# FPGA_Configuration.net
KiCad netlist of a schematic drawn in Altium Designer
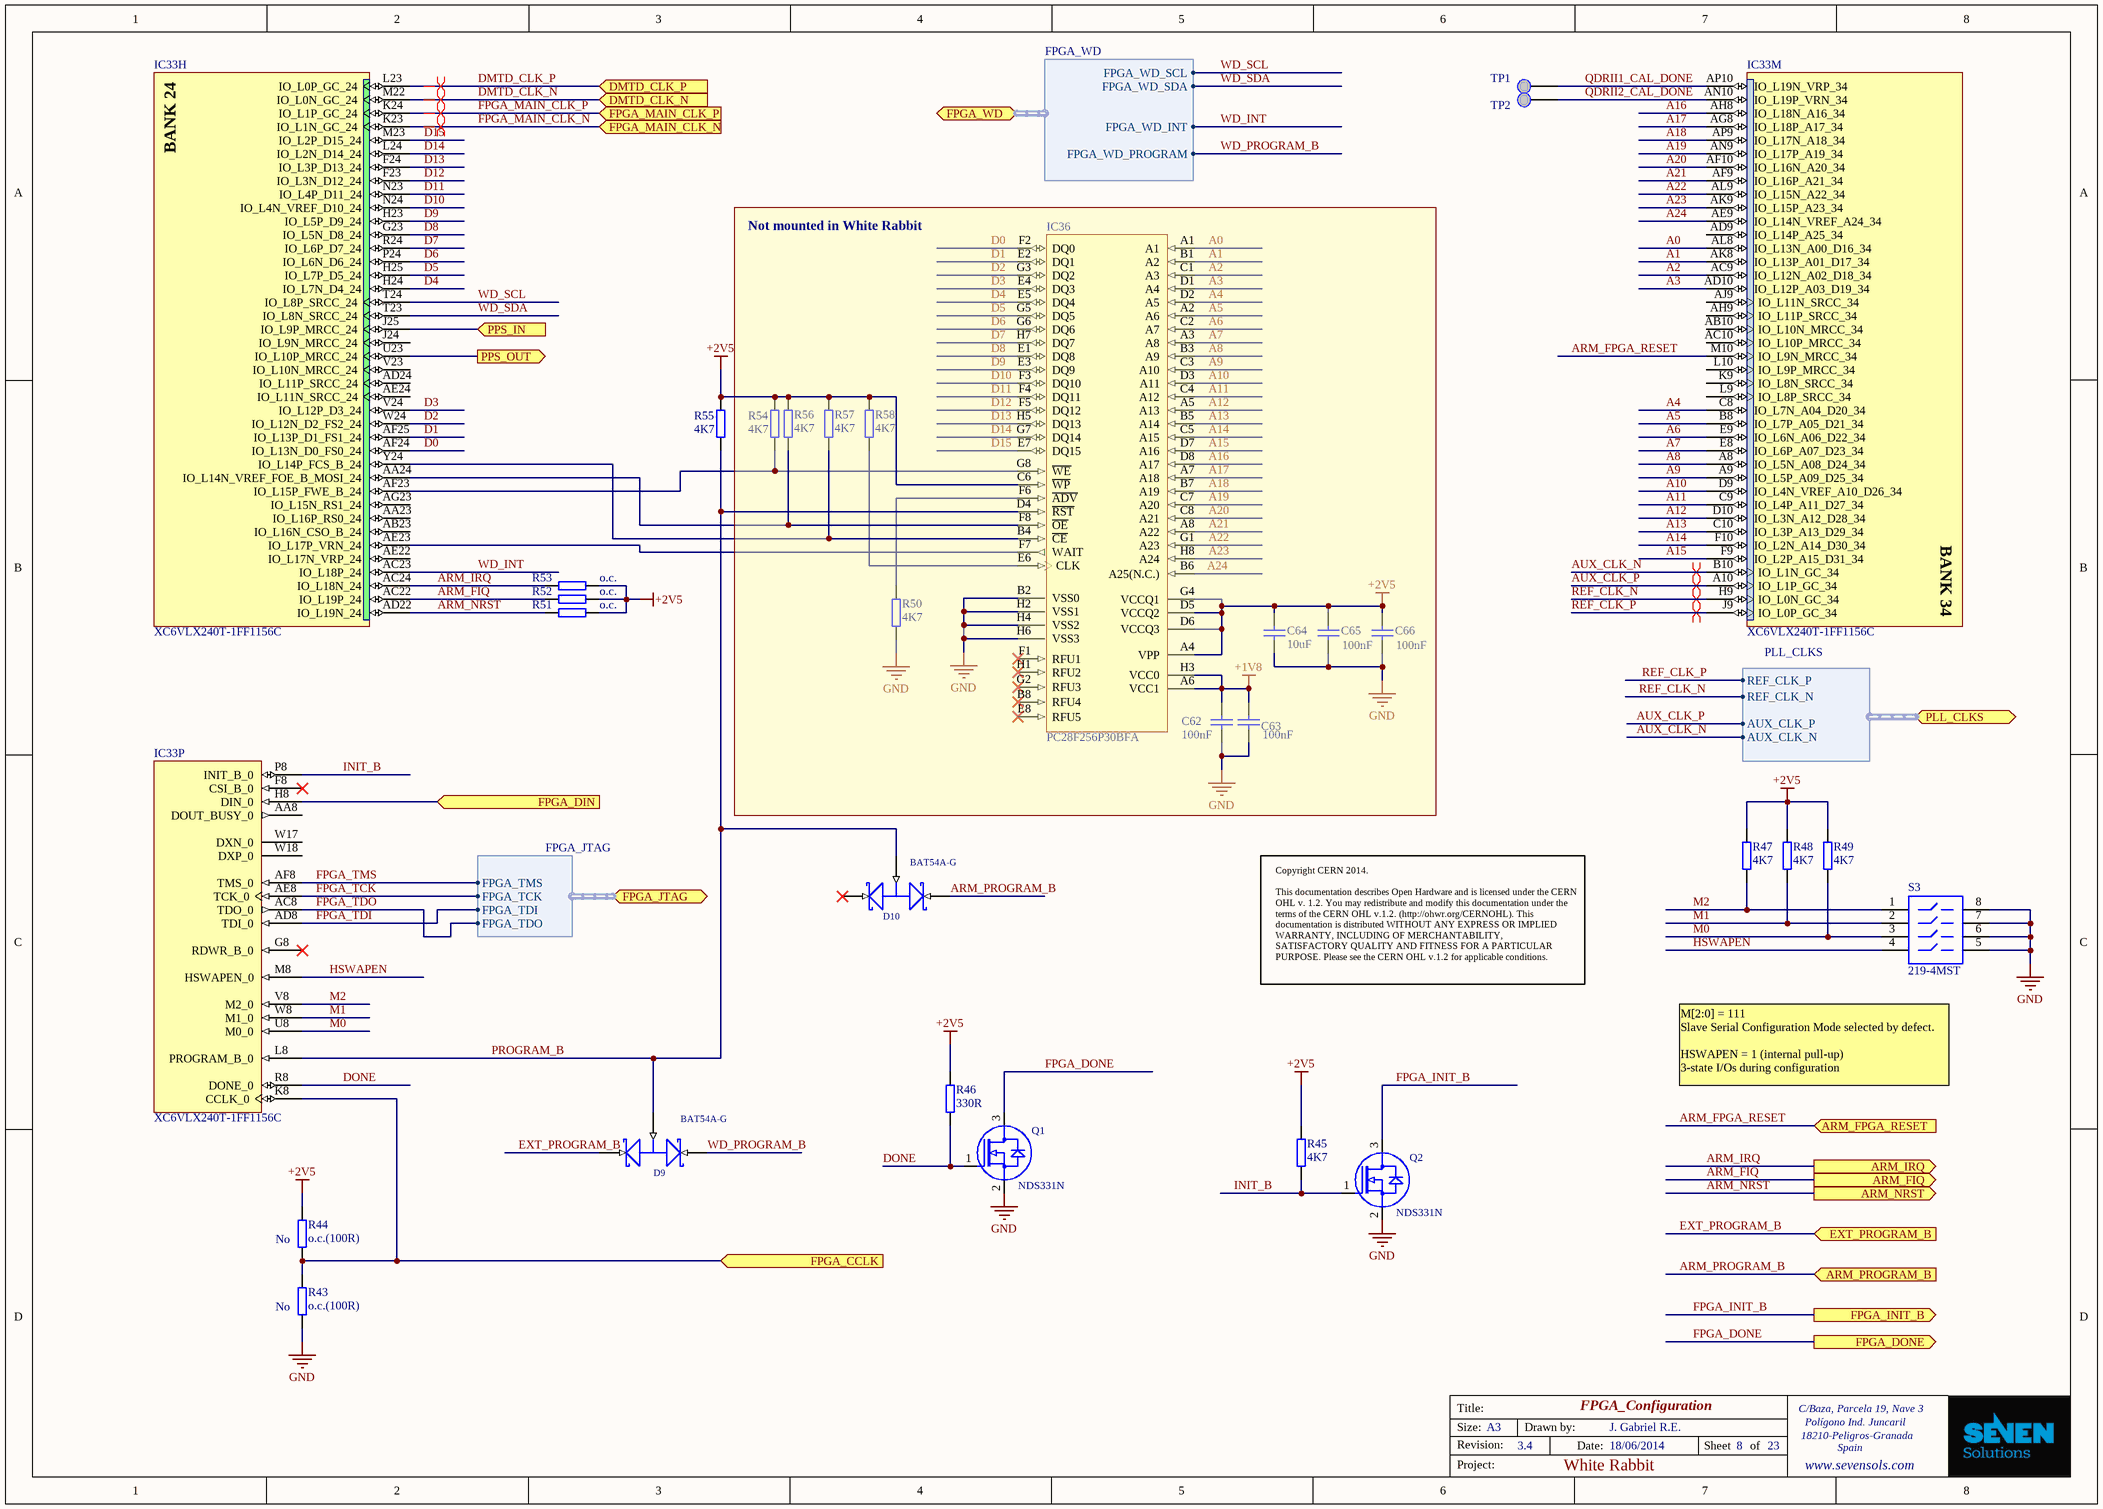
[diagram p0: FPGA_Configuration.SchDoc]

(export (version "E")
  (design (tool "Eeschema 10.0.6"))
  (components
    (comp (ref "C62")
      (value "100nF")
      (footprint "CC1005-0402")
      (description "Capacitor")
      (fields
        (field (name "TOLERANCE") "±10%")
        (field (name "VOLTAGE") "16V")
        (field (name "PUBLISHER") "Altium Limited")
      )
      (libsource (lib "wr_switch") (part "Cap"))
    )
    (comp (ref "C63")
      (value "100nF")
      (footprint "CC1005-0402")
      (description "Capacitor")
      (fields
        (field (name "TOLERANCE") "±10%")
        (field (name "VOLTAGE") "16V")
        (field (name "PUBLISHER") "Altium Limited")
      )
      (libsource (lib "wr_switch") (part "Cap"))
    )
    (comp (ref "C64")
      (value "10uF")
      (footprint "CC1608-0603")
      (description "Capacitor")
      (fields
        (field (name "TOLERANCE") "±20%")
        (field (name "VOLTAGE") "6.3V")
        (field (name "PUBLISHER") "Altium Limited")
      )
      (libsource (lib "wr_switch") (part "Cap"))
    )
    (comp (ref "C65")
      (value "100nF")
      (footprint "CC1005-0402")
      (description "Capacitor")
      (fields
        (field (name "TOLERANCE") "±10%")
        (field (name "VOLTAGE") "16V")
        (field (name "PUBLISHER") "Altium Limited")
      )
      (libsource (lib "wr_switch") (part "Cap"))
    )
    (comp (ref "C66")
      (value "100nF")
      (footprint "CC1005-0402")
      (description "Capacitor")
      (fields
        (field (name "TOLERANCE") "±10%")
        (field (name "VOLTAGE") "16V")
        (field (name "PUBLISHER") "Altium Limited")
      )
      (libsource (lib "wr_switch") (part "Cap"))
    )
    (comp (ref "D9")
      (value "BAT54A-G")
      (footprint "SOT23")
      (description "Schottky Barrier Double Diode")
      (fields (field (name "PUBLISHER") "Altium Limited"))
      (libsource (lib "wr_switch") (part "BAT54A.1"))
    )
    (comp (ref "D10")
      (value "BAT54A-G")
      (footprint "SOT23")
      (description "Schottky Barrier Double Diode")
      (fields (field (name "PUBLISHER") "Altium Limited"))
      (libsource (lib "wr_switch") (part "BAT54A.1"))
    )
    (comp (ref "IC33")
      (value "XC6VLX240T-1FF1156C")
      (footprint "FF1156")
      (fields (field (name "PUBLISHER") "Altium Limited"))
      (libsource (lib "") (part "XC6VLX240T-1FF1156C_1"))
    )
    (comp (ref "IC36")
      (value "PC28F256P30BFA")
      (footprint "BGA64C100P8X8_1300X1000X120")
      (description "NOR Flash Memory, 256Mbit")
      (libsource (lib "wr_switch") (part "PC28F256P30BFA"))
    )
    (comp (ref "Q1")
      (value "NDS331N")
      (footprint "SOT23-3")
      (description "N-Channel Logic Level Enhancement Mode Field Effect Transistor")
      (libsource (lib "wr_switch") (part "NDS331N"))
    )
    (comp (ref "Q2")
      (value "NDS331N")
      (footprint "SOT23-3")
      (description "N-Channel Logic Level Enhancement Mode Field Effect Transistor")
      (libsource (lib "wr_switch") (part "NDS331N"))
    )
    (comp (ref "R43")
      (value "o.c.(100R)")
      (footprint "0402")
      (description "SMD Resistor")
      (fields
        (field (name "TOLERANCE") "±1%")
        (field (name "MOUNTED") "No")
        (field (name "Comment") "100R(o.c.)")
      )
      (libsource (lib "wr_switch") (part "RES_SMD"))
    )
    (comp (ref "R44")
      (value "o.c.(100R)")
      (footprint "0402")
      (description "SMD Resistor")
      (fields
        (field (name "TOLERANCE") "±1%")
        (field (name "MOUNTED") "No")
        (field (name "Comment") "100R(o.c.)")
      )
      (libsource (lib "wr_switch") (part "RES_SMD"))
    )
    (comp (ref "R45")
      (value "4K7")
      (footprint "0402")
      (description "SMD Resistor")
      (fields (field (name "TOLERANCE") "±1%"))
      (libsource (lib "wr_switch") (part "RES_SMD"))
    )
    (comp (ref "R46")
      (value "330R")
      (footprint "0402")
      (description "SMD Resistor")
      (fields (field (name "TOLERANCE") "±1%"))
      (libsource (lib "wr_switch") (part "RES_SMD"))
    )
    (comp (ref "R47")
      (value "4K7")
      (footprint "0402")
      (description "SMD Resistor")
      (fields (field (name "TOLERANCE") "±1%"))
      (libsource (lib "wr_switch") (part "RES_SMD"))
    )
    (comp (ref "R48")
      (value "4K7")
      (footprint "0402")
      (description "SMD Resistor")
      (fields (field (name "TOLERANCE") "±1%"))
      (libsource (lib "wr_switch") (part "RES_SMD"))
    )
    (comp (ref "R49")
      (value "4K7")
      (footprint "0402")
      (description "SMD Resistor")
      (fields (field (name "TOLERANCE") "±1%"))
      (libsource (lib "wr_switch") (part "RES_SMD"))
    )
    (comp (ref "R50")
      (value "4K7")
      (footprint "0402")
      (description "SMD Resistor")
      (fields (field (name "TOLERANCE") "±1%"))
      (libsource (lib "wr_switch") (part "RES_SMD"))
    )
    (comp (ref "R51")
      (value "o.c.")
      (footprint "0402")
      (description "SMD Resistor")
      (libsource (lib "wr_switch") (part "RES_SMD"))
    )
    (comp (ref "R52")
      (value "o.c.")
      (footprint "0402")
      (description "SMD Resistor")
      (libsource (lib "wr_switch") (part "RES_SMD"))
    )
    (comp (ref "R53")
      (value "o.c.")
      (footprint "0402")
      (description "SMD Resistor")
      (libsource (lib "wr_switch") (part "RES_SMD"))
    )
    (comp (ref "R54")
      (value "4K7")
      (footprint "0402")
      (description "SMD Resistor")
      (fields (field (name "TOLERANCE") "±1%"))
      (libsource (lib "wr_switch") (part "RES_SMD"))
    )
    (comp (ref "R55")
      (value "4K7")
      (footprint "0402")
      (description "SMD Resistor")
      (fields (field (name "TOLERANCE") "±1%"))
      (libsource (lib "wr_switch") (part "RES_SMD"))
    )
    (comp (ref "R56")
      (value "4K7")
      (footprint "0402")
      (description "SMD Resistor")
      (fields (field (name "TOLERANCE") "±1%"))
      (libsource (lib "wr_switch") (part "RES_SMD"))
    )
    (comp (ref "R57")
      (value "4K7")
      (footprint "0402")
      (description "SMD Resistor")
      (fields (field (name "TOLERANCE") "±1%"))
      (libsource (lib "wr_switch") (part "RES_SMD"))
    )
    (comp (ref "R58")
      (value "4K7")
      (footprint "0402")
      (description "SMD Resistor")
      (fields (field (name "TOLERANCE") "±1%"))
      (libsource (lib "wr_switch") (part "RES_SMD"))
    )
    (comp (ref "S3")
      (value "219-4MST")
      (footprint "7S_WR:NHDS-8")
      (description "4 Positions DIP SWITCH")
      (fields (field (name "MANUFACTURER") "CTS Electrocomponents"))
      (libsource (lib "wr_switch") (part "SW-DIP4"))
    )
    (comp (ref "TP1")
      (value "Test Point")
      (footprint "TEST_PAD_1mm")
      (description "SMD 1mm Test Point")
      (libsource (lib "wr_switch") (part "TEST_POINT"))
    )
    (comp (ref "TP2")
      (value "Test Point")
      (footprint "TEST_PAD_1mm")
      (description "SMD 1mm Test Point")
      (libsource (lib "wr_switch") (part "TEST_POINT"))
    )
  )
  (nets
    (net (code "4") (name "+1V8") (class "Default")
      (node (ref "C62") (pin "2") (pinfunction "2_2") (pintype "passive"))
      (node (ref "C63") (pin "2") (pinfunction "2_2") (pintype "passive"))
      (node (ref "IC36") (pin "A6") (pinfunction "VCC1_A6") (pintype "power_in"))
      (node (ref "IC36") (pin "H3") (pinfunction "VCC0_H3") (pintype "power_in"))
    )
    (net (code "5") (name "+2V5") (class "Default")
      (node (ref "C64") (pin "2") (pinfunction "2_2") (pintype "passive"))
      (node (ref "C65") (pin "2") (pinfunction "2_2") (pintype "passive"))
      (node (ref "C66") (pin "2") (pinfunction "2_2") (pintype "passive"))
      (node (ref "IC36") (pin "A4") (pinfunction "VPP_A4") (pintype "passive"))
      (node (ref "IC36") (pin "C6") (pinfunction "~{WP}_C6") (pintype "input"))
      (node (ref "IC36") (pin "D5") (pinfunction "VCCQ2_D5") (pintype "power_in"))
      (node (ref "IC36") (pin "D6") (pinfunction "VCCQ3_D6") (pintype "power_in"))
      (node (ref "IC36") (pin "G4") (pinfunction "VCCQ1_G4") (pintype "power_in"))
      (node (ref "R44") (pin "2") (pinfunction "2_2") (pintype "passive"))
      (node (ref "R45") (pin "1") (pinfunction "1_1") (pintype "passive"))
      (node (ref "R46") (pin "2") (pinfunction "2_2") (pintype "passive"))
      (node (ref "R47") (pin "2") (pinfunction "2_2") (pintype "passive"))
      (node (ref "R48") (pin "2") (pinfunction "2_2") (pintype "passive"))
      (node (ref "R49") (pin "2") (pinfunction "2_2") (pintype "passive"))
      (node (ref "R51") (pin "1") (pinfunction "1_1") (pintype "passive"))
      (node (ref "R52") (pin "1") (pinfunction "1_1") (pintype "passive"))
      (node (ref "R53") (pin "1") (pinfunction "1_1") (pintype "passive"))
      (node (ref "R54") (pin "2") (pinfunction "2_2") (pintype "passive"))
      (node (ref "R55") (pin "2") (pinfunction "2_2") (pintype "passive"))
      (node (ref "R56") (pin "2") (pinfunction "2_2") (pintype "passive"))
      (node (ref "R57") (pin "2") (pinfunction "2_2") (pintype "passive"))
      (node (ref "R58") (pin "2") (pinfunction "2_2") (pintype "passive"))
    )
    (net (code "6") (name "/A0") (class "Default")
      (node (ref "IC33") (pin "AL8") (pinfunction "IO_L13N_A00_D16_34_AL8") (pintype "bidirectional"))
      (node (ref "IC36") (pin "A1") (pinfunction "A1_A1") (pintype "input"))
    )
    (net (code "7") (name "/A1") (class "Default")
      (node (ref "IC33") (pin "AK8") (pinfunction "IO_L13P_A01_D17_34_AK8") (pintype "bidirectional"))
      (node (ref "IC36") (pin "B1") (pinfunction "A2_B1") (pintype "input"))
    )
    (net (code "8") (name "/A2") (class "Default")
      (node (ref "IC33") (pin "AC9") (pinfunction "IO_L12N_A02_D18_34_AC9") (pintype "bidirectional"))
      (node (ref "IC36") (pin "C1") (pinfunction "A3_C1") (pintype "input"))
    )
    (net (code "9") (name "/A3") (class "Default")
      (node (ref "IC33") (pin "AD10") (pinfunction "IO_L12P_A03_D19_34_AD10") (pintype "bidirectional"))
      (node (ref "IC36") (pin "D1") (pinfunction "A4_D1") (pintype "input"))
    )
    (net (code "10") (name "/A4") (class "Default")
      (node (ref "IC33") (pin "C8") (pinfunction "IO_L7N_A04_D20_34_C8") (pintype "bidirectional"))
      (node (ref "IC36") (pin "D2") (pinfunction "A5_D2") (pintype "input"))
    )
    (net (code "11") (name "/A5") (class "Default")
      (node (ref "IC33") (pin "B8") (pinfunction "IO_L7P_A05_D21_34_B8") (pintype "bidirectional"))
      (node (ref "IC36") (pin "A2") (pinfunction "A6_A2") (pintype "input"))
    )
    (net (code "12") (name "/A6") (class "Default")
      (node (ref "IC33") (pin "E9") (pinfunction "IO_L6N_A06_D22_34_E9") (pintype "bidirectional"))
      (node (ref "IC36") (pin "C2") (pinfunction "A7_C2") (pintype "input"))
    )
    (net (code "13") (name "/A7") (class "Default")
      (node (ref "IC33") (pin "E8") (pinfunction "IO_L6P_A07_D23_34_E8") (pintype "bidirectional"))
      (node (ref "IC36") (pin "A3") (pinfunction "A8_A3") (pintype "input"))
    )
    (net (code "14") (name "/A8") (class "Default")
      (node (ref "IC33") (pin "A8") (pinfunction "IO_L5N_A08_D24_34_A8") (pintype "bidirectional"))
      (node (ref "IC36") (pin "B3") (pinfunction "A9_B3") (pintype "input"))
    )
    (net (code "15") (name "/A9") (class "Default")
      (node (ref "IC33") (pin "A9") (pinfunction "IO_L5P_A09_D25_34_A9") (pintype "bidirectional"))
      (node (ref "IC36") (pin "C3") (pinfunction "A10_C3") (pintype "input"))
    )
    (net (code "16") (name "/A10") (class "Default")
      (node (ref "IC33") (pin "D9") (pinfunction "IO_L4N_VREF_A10_D26_34_D9") (pintype "bidirectional"))
      (node (ref "IC36") (pin "D3") (pinfunction "A11_D3") (pintype "input"))
    )
    (net (code "17") (name "/A11") (class "Default")
      (node (ref "IC33") (pin "C9") (pinfunction "IO_L4P_A11_D27_34_C9") (pintype "bidirectional"))
      (node (ref "IC36") (pin "C4") (pinfunction "A12_C4") (pintype "input"))
    )
    (net (code "18") (name "/A12") (class "Default")
      (node (ref "IC33") (pin "D10") (pinfunction "IO_L3N_A12_D28_34_D10") (pintype "bidirectional"))
      (node (ref "IC36") (pin "A5") (pinfunction "A13_A5") (pintype "input"))
    )
    (net (code "19") (name "/A13") (class "Default")
      (node (ref "IC33") (pin "C10") (pinfunction "IO_L3P_A13_D29_34_C10") (pintype "bidirectional"))
      (node (ref "IC36") (pin "B5") (pinfunction "A14_B5") (pintype "input"))
    )
    (net (code "20") (name "/A14") (class "Default")
      (node (ref "IC33") (pin "F10") (pinfunction "IO_L2N_A14_D30_34_F10") (pintype "bidirectional"))
      (node (ref "IC36") (pin "C5") (pinfunction "A15_C5") (pintype "input"))
    )
    (net (code "21") (name "/A15") (class "Default")
      (node (ref "IC33") (pin "F9") (pinfunction "IO_L2P_A15_D31_34_F9") (pintype "bidirectional"))
      (node (ref "IC36") (pin "D7") (pinfunction "A16_D7") (pintype "input"))
    )
    (net (code "22") (name "/A16") (class "Default")
      (node (ref "IC33") (pin "AH8") (pinfunction "IO_L18N_A16_34_AH8") (pintype "bidirectional"))
      (node (ref "IC36") (pin "D8") (pinfunction "A17_D8") (pintype "input"))
    )
    (net (code "23") (name "/A17") (class "Default")
      (node (ref "IC33") (pin "AG8") (pinfunction "IO_L18P_A17_34_AG8") (pintype "bidirectional"))
      (node (ref "IC36") (pin "A7") (pinfunction "A18_A7") (pintype "input"))
    )
    (net (code "24") (name "/A18") (class "Default")
      (node (ref "IC33") (pin "AP9") (pinfunction "IO_L17N_A18_34_AP9") (pintype "bidirectional"))
      (node (ref "IC36") (pin "B7") (pinfunction "A19_B7") (pintype "input"))
    )
    (net (code "25") (name "/A19") (class "Default")
      (node (ref "IC33") (pin "AN9") (pinfunction "IO_L17P_A19_34_AN9") (pintype "bidirectional"))
      (node (ref "IC36") (pin "C7") (pinfunction "A20_C7") (pintype "input"))
    )
    (net (code "26") (name "/A20") (class "Default")
      (node (ref "IC33") (pin "AF10") (pinfunction "IO_L16N_A20_34_AF10") (pintype "bidirectional"))
      (node (ref "IC36") (pin "C8") (pinfunction "A21_C8") (pintype "input"))
    )
    (net (code "27") (name "/A21") (class "Default")
      (node (ref "IC33") (pin "AF9") (pinfunction "IO_L16P_A21_34_AF9") (pintype "bidirectional"))
      (node (ref "IC36") (pin "A8") (pinfunction "A22_A8") (pintype "input"))
    )
    (net (code "28") (name "/A22") (class "Default")
      (node (ref "IC33") (pin "AL9") (pinfunction "IO_L15N_A22_34_AL9") (pintype "bidirectional"))
      (node (ref "IC36") (pin "G1") (pinfunction "A23_G1") (pintype "input"))
    )
    (net (code "29") (name "/A23") (class "Default")
      (node (ref "IC33") (pin "AK9") (pinfunction "IO_L15P_A23_34_AK9") (pintype "bidirectional"))
      (node (ref "IC36") (pin "H8") (pinfunction "A24_H8") (pintype "input"))
    )
    (net (code "30") (name "/A24") (class "Default")
      (node (ref "IC33") (pin "AE9") (pinfunction "IO_L14N_VREF_A24_34_AE9") (pintype "bidirectional"))
      (node (ref "IC36") (pin "B6") (pinfunction "A25(N.C.)_B6") (pintype "input"))
    )
    (net (code "31") (name "/ARM_FIQ") (class "Default")
      (node (ref "IC33") (pin "AC22") (pinfunction "IO_L19P_24_AC22") (pintype "bidirectional"))
      (node (ref "R52") (pin "2") (pinfunction "2_2") (pintype "passive"))
    )
    (net (code "32") (name "/ARM_FPGA_RESET") (class "Default")
      (node (ref "IC33") (pin "M10") (pinfunction "IO_L9N_MRCC_34_M10") (pintype "bidirectional"))
    )
    (net (code "33") (name "/ARM_IRQ") (class "Default")
      (node (ref "IC33") (pin "AC24") (pinfunction "IO_L18N_24_AC24") (pintype "bidirectional"))
      (node (ref "R53") (pin "2") (pinfunction "2_2") (pintype "passive"))
    )
    (net (code "34") (name "/ARM_NRST") (class "Default")
      (node (ref "IC33") (pin "AD22") (pinfunction "IO_L19N_24_AD22") (pintype "bidirectional"))
      (node (ref "R51") (pin "2") (pinfunction "2_2") (pintype "passive"))
    )
    (net (code "35") (name "/ARM_PROGRAM_B") (class "Default")
      (node (ref "D10") (pin "2") (pinfunction "K2_2") (pintype "input"))
    )
    (net (code "36") (name "/AUX_CLK_N") (class "Default")
      (node (ref "IC33") (pin "B10") (pinfunction "IO_L1N_GC_34_B10") (pintype "bidirectional"))
    )
    (net (code "37") (name "/AUX_CLK_P") (class "Default")
      (node (ref "IC33") (pin "A10") (pinfunction "IO_L1P_GC_34_A10") (pintype "bidirectional"))
    )
    (net (code "38") (name "/D0") (class "Default")
      (node (ref "IC33") (pin "AF24") (pinfunction "IO_L13N_D0_FS0_24_AF24") (pintype "bidirectional"))
      (node (ref "IC36") (pin "F2") (pinfunction "DQ0_F2") (pintype "bidirectional"))
    )
    (net (code "39") (name "/D1") (class "Default")
      (node (ref "IC33") (pin "AF25") (pinfunction "IO_L13P_D1_FS1_24_AF25") (pintype "bidirectional"))
      (node (ref "IC36") (pin "E2") (pinfunction "DQ1_E2") (pintype "bidirectional"))
    )
    (net (code "40") (name "/D2") (class "Default")
      (node (ref "IC33") (pin "W24") (pinfunction "IO_L12N_D2_FS2_24_W24") (pintype "bidirectional"))
      (node (ref "IC36") (pin "G3") (pinfunction "DQ2_G3") (pintype "bidirectional"))
    )
    (net (code "41") (name "/D3") (class "Default")
      (node (ref "IC33") (pin "V24") (pinfunction "IO_L12P_D3_24_V24") (pintype "bidirectional"))
      (node (ref "IC36") (pin "E4") (pinfunction "DQ3_E4") (pintype "bidirectional"))
    )
    (net (code "42") (name "/D4") (class "Default")
      (node (ref "IC33") (pin "H24") (pinfunction "IO_L7N_D4_24_H24") (pintype "bidirectional"))
      (node (ref "IC36") (pin "E5") (pinfunction "DQ4_E5") (pintype "bidirectional"))
    )
    (net (code "43") (name "/D5") (class "Default")
      (node (ref "IC33") (pin "H25") (pinfunction "IO_L7P_D5_24_H25") (pintype "bidirectional"))
      (node (ref "IC36") (pin "G5") (pinfunction "DQ5_G5") (pintype "bidirectional"))
    )
    (net (code "44") (name "/D6") (class "Default")
      (node (ref "IC33") (pin "P24") (pinfunction "IO_L6N_D6_24_P24") (pintype "bidirectional"))
      (node (ref "IC36") (pin "G6") (pinfunction "DQ6_G6") (pintype "bidirectional"))
    )
    (net (code "45") (name "/D7") (class "Default")
      (node (ref "IC33") (pin "R24") (pinfunction "IO_L6P_D7_24_R24") (pintype "bidirectional"))
      (node (ref "IC36") (pin "H7") (pinfunction "DQ7_H7") (pintype "bidirectional"))
    )
    (net (code "46") (name "/D8") (class "Default")
      (node (ref "IC33") (pin "G23") (pinfunction "IO_L5N_D8_24_G23") (pintype "bidirectional"))
      (node (ref "IC36") (pin "E1") (pinfunction "DQ8_E1") (pintype "bidirectional"))
    )
    (net (code "47") (name "/D9") (class "Default")
      (node (ref "IC33") (pin "H23") (pinfunction "IO_L5P_D9_24_H23") (pintype "bidirectional"))
      (node (ref "IC36") (pin "E3") (pinfunction "DQ9_E3") (pintype "bidirectional"))
    )
    (net (code "48") (name "/D10") (class "Default")
      (node (ref "IC33") (pin "N24") (pinfunction "IO_L4N_VREF_D10_24_N24") (pintype "bidirectional"))
      (node (ref "IC36") (pin "F3") (pinfunction "DQ10_F3") (pintype "bidirectional"))
    )
    (net (code "49") (name "/D11") (class "Default")
      (node (ref "IC33") (pin "N23") (pinfunction "IO_L4P_D11_24_N23") (pintype "bidirectional"))
      (node (ref "IC36") (pin "F4") (pinfunction "DQ11_F4") (pintype "bidirectional"))
    )
    (net (code "50") (name "/D12") (class "Default")
      (node (ref "IC33") (pin "F23") (pinfunction "IO_L3N_D12_24_F23") (pintype "bidirectional"))
      (node (ref "IC36") (pin "F5") (pinfunction "DQ12_F5") (pintype "bidirectional"))
    )
    (net (code "51") (name "/D13") (class "Default")
      (node (ref "IC33") (pin "F24") (pinfunction "IO_L3P_D13_24_F24") (pintype "bidirectional"))
      (node (ref "IC36") (pin "H5") (pinfunction "DQ13_H5") (pintype "bidirectional"))
    )
    (net (code "52") (name "/D14") (class "Default")
      (node (ref "IC33") (pin "L24") (pinfunction "IO_L2N_D14_24_L24") (pintype "bidirectional"))
      (node (ref "IC36") (pin "G7") (pinfunction "DQ14_G7") (pintype "bidirectional"))
    )
    (net (code "53") (name "/D15") (class "Default")
      (node (ref "IC33") (pin "M23") (pinfunction "IO_L2P_D15_24_M23") (pintype "bidirectional"))
      (node (ref "IC36") (pin "E7") (pinfunction "DQ15_E7") (pintype "bidirectional"))
    )
    (net (code "54") (name "/DMTD_CLK_N") (class "Default")
      (node (ref "IC33") (pin "M22") (pinfunction "IO_L0N_GC_24_M22") (pintype "bidirectional"))
    )
    (net (code "55") (name "/DMTD_CLK_P") (class "Default")
      (node (ref "IC33") (pin "L23") (pinfunction "IO_L0P_GC_24_L23") (pintype "bidirectional"))
    )
    (net (code "56") (name "/DONE") (class "Default")
      (node (ref "IC33") (pin "R8") (pinfunction "DONE_0_R8") (pintype "bidirectional"))
      (node (ref "Q1") (pin "1") (pinfunction "GATE_1") (pintype "passive"))
      (node (ref "R46") (pin "1") (pinfunction "1_1") (pintype "passive"))
    )
    (net (code "57") (name "/EXT_PROGRAM_B") (class "Default")
      (node (ref "D9") (pin "1") (pinfunction "K1_1") (pintype "input"))
    )
    (net (code "58") (name "/FPGA_CCLK") (class "Default")
      (node (ref "IC33") (pin "K8") (pinfunction "CCLK_0_K8") (pintype "bidirectional"))
      (node (ref "R43") (pin "2") (pinfunction "2_2") (pintype "passive"))
      (node (ref "R44") (pin "1") (pinfunction "1_1") (pintype "passive"))
    )
    (net (code "59") (name "/FPGA_DIN") (class "Default")
      (node (ref "IC33") (pin "H8") (pinfunction "DIN_0_H8") (pintype "input"))
    )
    (net (code "60") (name "/FPGA_DONE") (class "Default")
      (node (ref "Q1") (pin "3") (pinfunction "DRAIN_3") (pintype "passive"))
    )
    (net (code "61") (name "/FPGA_INIT_B") (class "Default")
      (node (ref "Q2") (pin "3") (pinfunction "DRAIN_3") (pintype "passive"))
    )
    (net (code "62") (name "/FPGA_MAIN_CLK_N") (class "Default")
      (node (ref "IC33") (pin "K23") (pinfunction "IO_L1N_GC_24_K23") (pintype "bidirectional"))
    )
    (net (code "63") (name "/FPGA_MAIN_CLK_P") (class "Default")
      (node (ref "IC33") (pin "K24") (pinfunction "IO_L1P_GC_24_K24") (pintype "bidirectional"))
    )
    (net (code "64") (name "/FPGA_TCK") (class "Default")
      (node (ref "IC33") (pin "AE8") (pinfunction "TCK_0_AE8") (pintype "input"))
    )
    (net (code "65") (name "/FPGA_TDI") (class "Default")
      (node (ref "IC33") (pin "AD8") (pinfunction "TDI_0_AD8") (pintype "input"))
    )
    (net (code "66") (name "/FPGA_TDO") (class "Default")
      (node (ref "IC33") (pin "AC8") (pinfunction "TDO_0_AC8") (pintype "output"))
    )
    (net (code "67") (name "/FPGA_TMS") (class "Default")
      (node (ref "IC33") (pin "AF8") (pinfunction "TMS_0_AF8") (pintype "input"))
    )
    (net (code "68") (name "/HSWAPEN") (class "Default")
      (node (ref "IC33") (pin "M8") (pinfunction "HSWAPEN_0_M8") (pintype "input"))
      (node (ref "S3") (pin "4") (pinfunction "4_4") (pintype "passive"))
    )
    (net (code "69") (name "/INIT_B") (class "Default")
      (node (ref "IC33") (pin "P8") (pinfunction "INIT_B_0_P8") (pintype "bidirectional"))
      (node (ref "Q2") (pin "1") (pinfunction "GATE_1") (pintype "passive"))
      (node (ref "R45") (pin "2") (pinfunction "2_2") (pintype "passive"))
    )
    (net (code "70") (name "/M0") (class "Default")
      (node (ref "IC33") (pin "U8") (pinfunction "M0_0_U8") (pintype "input"))
      (node (ref "R49") (pin "1") (pinfunction "1_1") (pintype "passive"))
      (node (ref "S3") (pin "3") (pinfunction "3_3") (pintype "passive"))
    )
    (net (code "71") (name "/M1") (class "Default")
      (node (ref "IC33") (pin "W8") (pinfunction "M1_0_W8") (pintype "input"))
      (node (ref "R48") (pin "1") (pinfunction "1_1") (pintype "passive"))
      (node (ref "S3") (pin "2") (pinfunction "2_2") (pintype "passive"))
    )
    (net (code "72") (name "/M2") (class "Default")
      (node (ref "IC33") (pin "V8") (pinfunction "M2_0_V8") (pintype "input"))
      (node (ref "R47") (pin "1") (pinfunction "1_1") (pintype "passive"))
      (node (ref "S3") (pin "1") (pinfunction "1_1") (pintype "passive"))
    )
    (net (code "73") (name "/PPS_IN") (class "Default")
      (node (ref "IC33") (pin "J25") (pinfunction "IO_L9P_MRCC_24_J25") (pintype "bidirectional"))
    )
    (net (code "74") (name "/PPS_OUT") (class "Default")
      (node (ref "IC33") (pin "U23") (pinfunction "IO_L10P_MRCC_24_U23") (pintype "bidirectional"))
    )
    (net (code "75") (name "/PROGRAM_B") (class "Default")
      (node (ref "D10") (pin "3") (pinfunction "A_3") (pintype "input"))
      (node (ref "D9") (pin "3") (pinfunction "A_3") (pintype "input"))
      (node (ref "IC33") (pin "L8") (pinfunction "PROGRAM_B_0_L8") (pintype "input"))
      (node (ref "IC36") (pin "D4") (pinfunction "~{RST}_D4") (pintype "input"))
      (node (ref "R55") (pin "1") (pinfunction "1_1") (pintype "passive"))
    )
    (net (code "76") (name "/QDRII1_CAL_DONE") (class "Default")
      (node (ref "IC33") (pin "AP10") (pinfunction "IO_L19N_VRP_34_AP10") (pintype "bidirectional"))
      (node (ref "TP1") (pin "1") (pinfunction "TP_1") (pintype "passive"))
    )
    (net (code "77") (name "/QDRII2_CAL_DONE") (class "Default")
      (node (ref "IC33") (pin "AN10") (pinfunction "IO_L19P_VRN_34_AN10") (pintype "bidirectional"))
      (node (ref "TP2") (pin "1") (pinfunction "TP_1") (pintype "passive"))
    )
    (net (code "78") (name "/REF_CLK_N") (class "Default")
      (node (ref "IC33") (pin "H9") (pinfunction "IO_L0N_GC_34_H9") (pintype "bidirectional"))
    )
    (net (code "79") (name "/REF_CLK_P") (class "Default")
      (node (ref "IC33") (pin "J9") (pinfunction "IO_L0P_GC_34_J9") (pintype "bidirectional"))
    )
    (net (code "80") (name "/WD_INT") (class "Default")
      (node (ref "IC33") (pin "AC23") (pinfunction "IO_L18P_24_AC23") (pintype "bidirectional"))
    )
    (net (code "81") (name "/WD_PROGRAM_B") (class "Default")
      (node (ref "D9") (pin "2") (pinfunction "K2_2") (pintype "input"))
    )
    (net (code "82") (name "/WD_SCL") (class "Default")
      (node (ref "IC33") (pin "T24") (pinfunction "IO_L8P_SRCC_24_T24") (pintype "bidirectional"))
    )
    (net (code "83") (name "/WD_SDA") (class "Default")
      (node (ref "IC33") (pin "T23") (pinfunction "IO_L8N_SRCC_24_T23") (pintype "bidirectional"))
    )
    (net (code "87") (name "GND") (class "Default")
      (node (ref "C62") (pin "1") (pinfunction "1_1") (pintype "passive"))
      (node (ref "C63") (pin "1") (pinfunction "1_1") (pintype "passive"))
      (node (ref "C64") (pin "1") (pinfunction "1_1") (pintype "passive"))
      (node (ref "C65") (pin "1") (pinfunction "1_1") (pintype "passive"))
      (node (ref "C66") (pin "1") (pinfunction "1_1") (pintype "passive"))
      (node (ref "IC36") (pin "B2") (pinfunction "VSS0_B2") (pintype "power_in"))
      (node (ref "IC36") (pin "H2") (pinfunction "VSS1_H2") (pintype "power_in"))
      (node (ref "IC36") (pin "H4") (pinfunction "VSS2_H4") (pintype "power_in"))
      (node (ref "IC36") (pin "H6") (pinfunction "VSS3_H6") (pintype "power_in"))
      (node (ref "Q1") (pin "2") (pinfunction "SOURCE_2") (pintype "passive"))
      (node (ref "Q2") (pin "2") (pinfunction "SOURCE_2") (pintype "passive"))
      (node (ref "R43") (pin "1") (pinfunction "1_1") (pintype "passive"))
      (node (ref "R50") (pin "1") (pinfunction "1_1") (pintype "passive"))
      (node (ref "S3") (pin "5") (pinfunction "5_5") (pintype "passive"))
      (node (ref "S3") (pin "6") (pinfunction "6_6") (pintype "passive"))
      (node (ref "S3") (pin "7") (pinfunction "7_7") (pintype "passive"))
      (node (ref "S3") (pin "8") (pinfunction "8_8") (pintype "passive"))
    )
    (net (code "88") (name "Net-(IC33H-IO_L14N_VREF_FOE_B_MOSI_24)") (class "Default")
      (node (ref "IC33") (pin "AA24") (pinfunction "IO_L14N_VREF_FOE_B_MOSI_24_AA24") (pintype "bidirectional"))
      (node (ref "IC36") (pin "F8") (pinfunction "~{OE}_F8") (pintype "input"))
      (node (ref "R56") (pin "1") (pinfunction "1_1") (pintype "passive"))
    )
    (net (code "89") (name "Net-(IC33H-IO_L14P_FCS_B_24)") (class "Default")
      (node (ref "IC33") (pin "Y24") (pinfunction "IO_L14P_FCS_B_24_Y24") (pintype "bidirectional"))
      (node (ref "IC36") (pin "B4") (pinfunction "~{CE}_B4") (pintype "input"))
      (node (ref "R57") (pin "1") (pinfunction "1_1") (pintype "passive"))
    )
    (net (code "90") (name "Net-(IC33H-IO_L15P_FWE_B_24)") (class "Default")
      (node (ref "IC33") (pin "AF23") (pinfunction "IO_L15P_FWE_B_24_AF23") (pintype "bidirectional"))
      (node (ref "IC36") (pin "G8") (pinfunction "~{WE}_G8") (pintype "input"))
      (node (ref "R54") (pin "1") (pinfunction "1_1") (pintype "passive"))
    )
    (net (code "91") (name "Net-(IC33H-IO_L17P_VRN_24)") (class "Default")
      (node (ref "IC33") (pin "AE23") (pinfunction "IO_L17P_VRN_24_AE23") (pintype "bidirectional"))
      (node (ref "IC36") (pin "F7") (pinfunction "WAIT_F7") (pintype "output"))
    )
    (net (code "92") (name "Net-(IC36-CLK)") (class "Default")
      (node (ref "IC36") (pin "E6") (pinfunction "CLK_E6") (pintype "input"))
      (node (ref "R58") (pin "1") (pinfunction "1_1") (pintype "passive"))
    )
    (net (code "93") (name "Net-(IC36-~{ADV})") (class "Default")
      (node (ref "IC36") (pin "F6") (pinfunction "~{ADV}_F6") (pintype "input"))
      (node (ref "R50") (pin "2") (pinfunction "2_2") (pintype "passive"))
    )
    (net (code "94") (name "unconnected-(D10-K1-Pad1)") (class "Default")
      (node (ref "D10") (pin "1") (pinfunction "K1_1") (pintype "input+no_connect"))
    )
    (net (code "95") (name "unconnected-(IC33H-IO_L9N_MRCC_24-PadJ24)") (class "Default")
      (node (ref "IC33") (pin "J24") (pinfunction "IO_L9N_MRCC_24_J24") (pintype "bidirectional"))
    )
    (net (code "96") (name "unconnected-(IC33H-IO_L10N_MRCC_24-PadV23)") (class "Default")
      (node (ref "IC33") (pin "V23") (pinfunction "IO_L10N_MRCC_24_V23") (pintype "bidirectional"))
    )
    (net (code "97") (name "unconnected-(IC33H-IO_L11N_SRCC_24-PadAE24)") (class "Default")
      (node (ref "IC33") (pin "AE24") (pinfunction "IO_L11N_SRCC_24_AE24") (pintype "bidirectional"))
    )
    (net (code "98") (name "unconnected-(IC33H-IO_L11P_SRCC_24-PadAD24)") (class "Default")
      (node (ref "IC33") (pin "AD24") (pinfunction "IO_L11P_SRCC_24_AD24") (pintype "bidirectional"))
    )
    (net (code "99") (name "unconnected-(IC33H-IO_L15N_RS1_24-PadAG23)") (class "Default")
      (node (ref "IC33") (pin "AG23") (pinfunction "IO_L15N_RS1_24_AG23") (pintype "bidirectional"))
    )
    (net (code "100") (name "unconnected-(IC33H-IO_L16N_CSO_B_24-PadAB23)") (class "Default")
      (node (ref "IC33") (pin "AB23") (pinfunction "IO_L16N_CSO_B_24_AB23") (pintype "bidirectional"))
    )
    (net (code "101") (name "unconnected-(IC33H-IO_L16P_RS0_24-PadAA23)") (class "Default")
      (node (ref "IC33") (pin "AA23") (pinfunction "IO_L16P_RS0_24_AA23") (pintype "bidirectional"))
    )
    (net (code "102") (name "unconnected-(IC33H-IO_L17N_VRP_24-PadAE22)") (class "Default")
      (node (ref "IC33") (pin "AE22") (pinfunction "IO_L17N_VRP_24_AE22") (pintype "bidirectional"))
    )
    (net (code "103") (name "unconnected-(IC33M-IO_L8N_SRCC_34-PadK9)") (class "Default")
      (node (ref "IC33") (pin "K9") (pinfunction "IO_L8N_SRCC_34_K9") (pintype "bidirectional"))
    )
    (net (code "104") (name "unconnected-(IC33M-IO_L8P_SRCC_34-PadL9)") (class "Default")
      (node (ref "IC33") (pin "L9") (pinfunction "IO_L8P_SRCC_34_L9") (pintype "bidirectional"))
    )
    (net (code "105") (name "unconnected-(IC33M-IO_L9P_MRCC_34-PadL10)") (class "Default")
      (node (ref "IC33") (pin "L10") (pinfunction "IO_L9P_MRCC_34_L10") (pintype "bidirectional"))
    )
    (net (code "106") (name "unconnected-(IC33M-IO_L10N_MRCC_34-PadAB10)") (class "Default")
      (node (ref "IC33") (pin "AB10") (pinfunction "IO_L10N_MRCC_34_AB10") (pintype "bidirectional"))
    )
    (net (code "107") (name "unconnected-(IC33M-IO_L10P_MRCC_34-PadAC10)") (class "Default")
      (node (ref "IC33") (pin "AC10") (pinfunction "IO_L10P_MRCC_34_AC10") (pintype "bidirectional"))
    )
    (net (code "108") (name "unconnected-(IC33M-IO_L11N_SRCC_34-PadAJ9)") (class "Default")
      (node (ref "IC33") (pin "AJ9") (pinfunction "IO_L11N_SRCC_34_AJ9") (pintype "bidirectional"))
    )
    (net (code "109") (name "unconnected-(IC33M-IO_L11P_SRCC_34-PadAH9)") (class "Default")
      (node (ref "IC33") (pin "AH9") (pinfunction "IO_L11P_SRCC_34_AH9") (pintype "bidirectional"))
    )
    (net (code "110") (name "unconnected-(IC33M-IO_L14P_A25_34-PadAD9)") (class "Default")
      (node (ref "IC33") (pin "AD9") (pinfunction "IO_L14P_A25_34_AD9") (pintype "bidirectional"))
    )
    (net (code "111") (name "unconnected-(IC33P-CSI_B_0-PadF8)") (class "Default")
      (node (ref "IC33") (pin "F8") (pinfunction "CSI_B_0_F8") (pintype "input+no_connect"))
    )
    (net (code "112") (name "unconnected-(IC33P-DOUT_BUSY_0-PadAA8)") (class "Default")
      (node (ref "IC33") (pin "AA8") (pinfunction "DOUT_BUSY_0_AA8") (pintype "output"))
    )
    (net (code "113") (name "unconnected-(IC33P-DXN_0-PadW17)") (class "Default")
      (node (ref "IC33") (pin "W17") (pinfunction "DXN_0_W17") (pintype "passive"))
    )
    (net (code "114") (name "unconnected-(IC33P-DXP_0-PadW18)") (class "Default")
      (node (ref "IC33") (pin "W18") (pinfunction "DXP_0_W18") (pintype "passive"))
    )
    (net (code "115") (name "unconnected-(IC33P-RDWR_B_0-PadG8)") (class "Default")
      (node (ref "IC33") (pin "G8") (pinfunction "RDWR_B_0_G8") (pintype "input+no_connect"))
    )
    (net (code "116") (name "unconnected-(IC36-RFU1-PadF1)") (class "Default")
      (node (ref "IC36") (pin "F1") (pinfunction "RFU1_F1") (pintype "input+no_connect"))
    )
    (net (code "117") (name "unconnected-(IC36-RFU2-PadH1)") (class "Default")
      (node (ref "IC36") (pin "H1") (pinfunction "RFU2_H1") (pintype "input+no_connect"))
    )
    (net (code "118") (name "unconnected-(IC36-RFU3-PadG2)") (class "Default")
      (node (ref "IC36") (pin "G2") (pinfunction "RFU3_G2") (pintype "input+no_connect"))
    )
    (net (code "119") (name "unconnected-(IC36-RFU4-PadB8)") (class "Default")
      (node (ref "IC36") (pin "B8") (pinfunction "RFU4_B8") (pintype "input+no_connect"))
    )
    (net (code "120") (name "unconnected-(IC36-RFU5-PadE8)") (class "Default")
      (node (ref "IC36") (pin "E8") (pinfunction "RFU5_E8") (pintype "input+no_connect"))
    )
  )
)
